# USB_GPIO_interface_V3.net
KiCad netlist of a schematic drawn in EAGLE
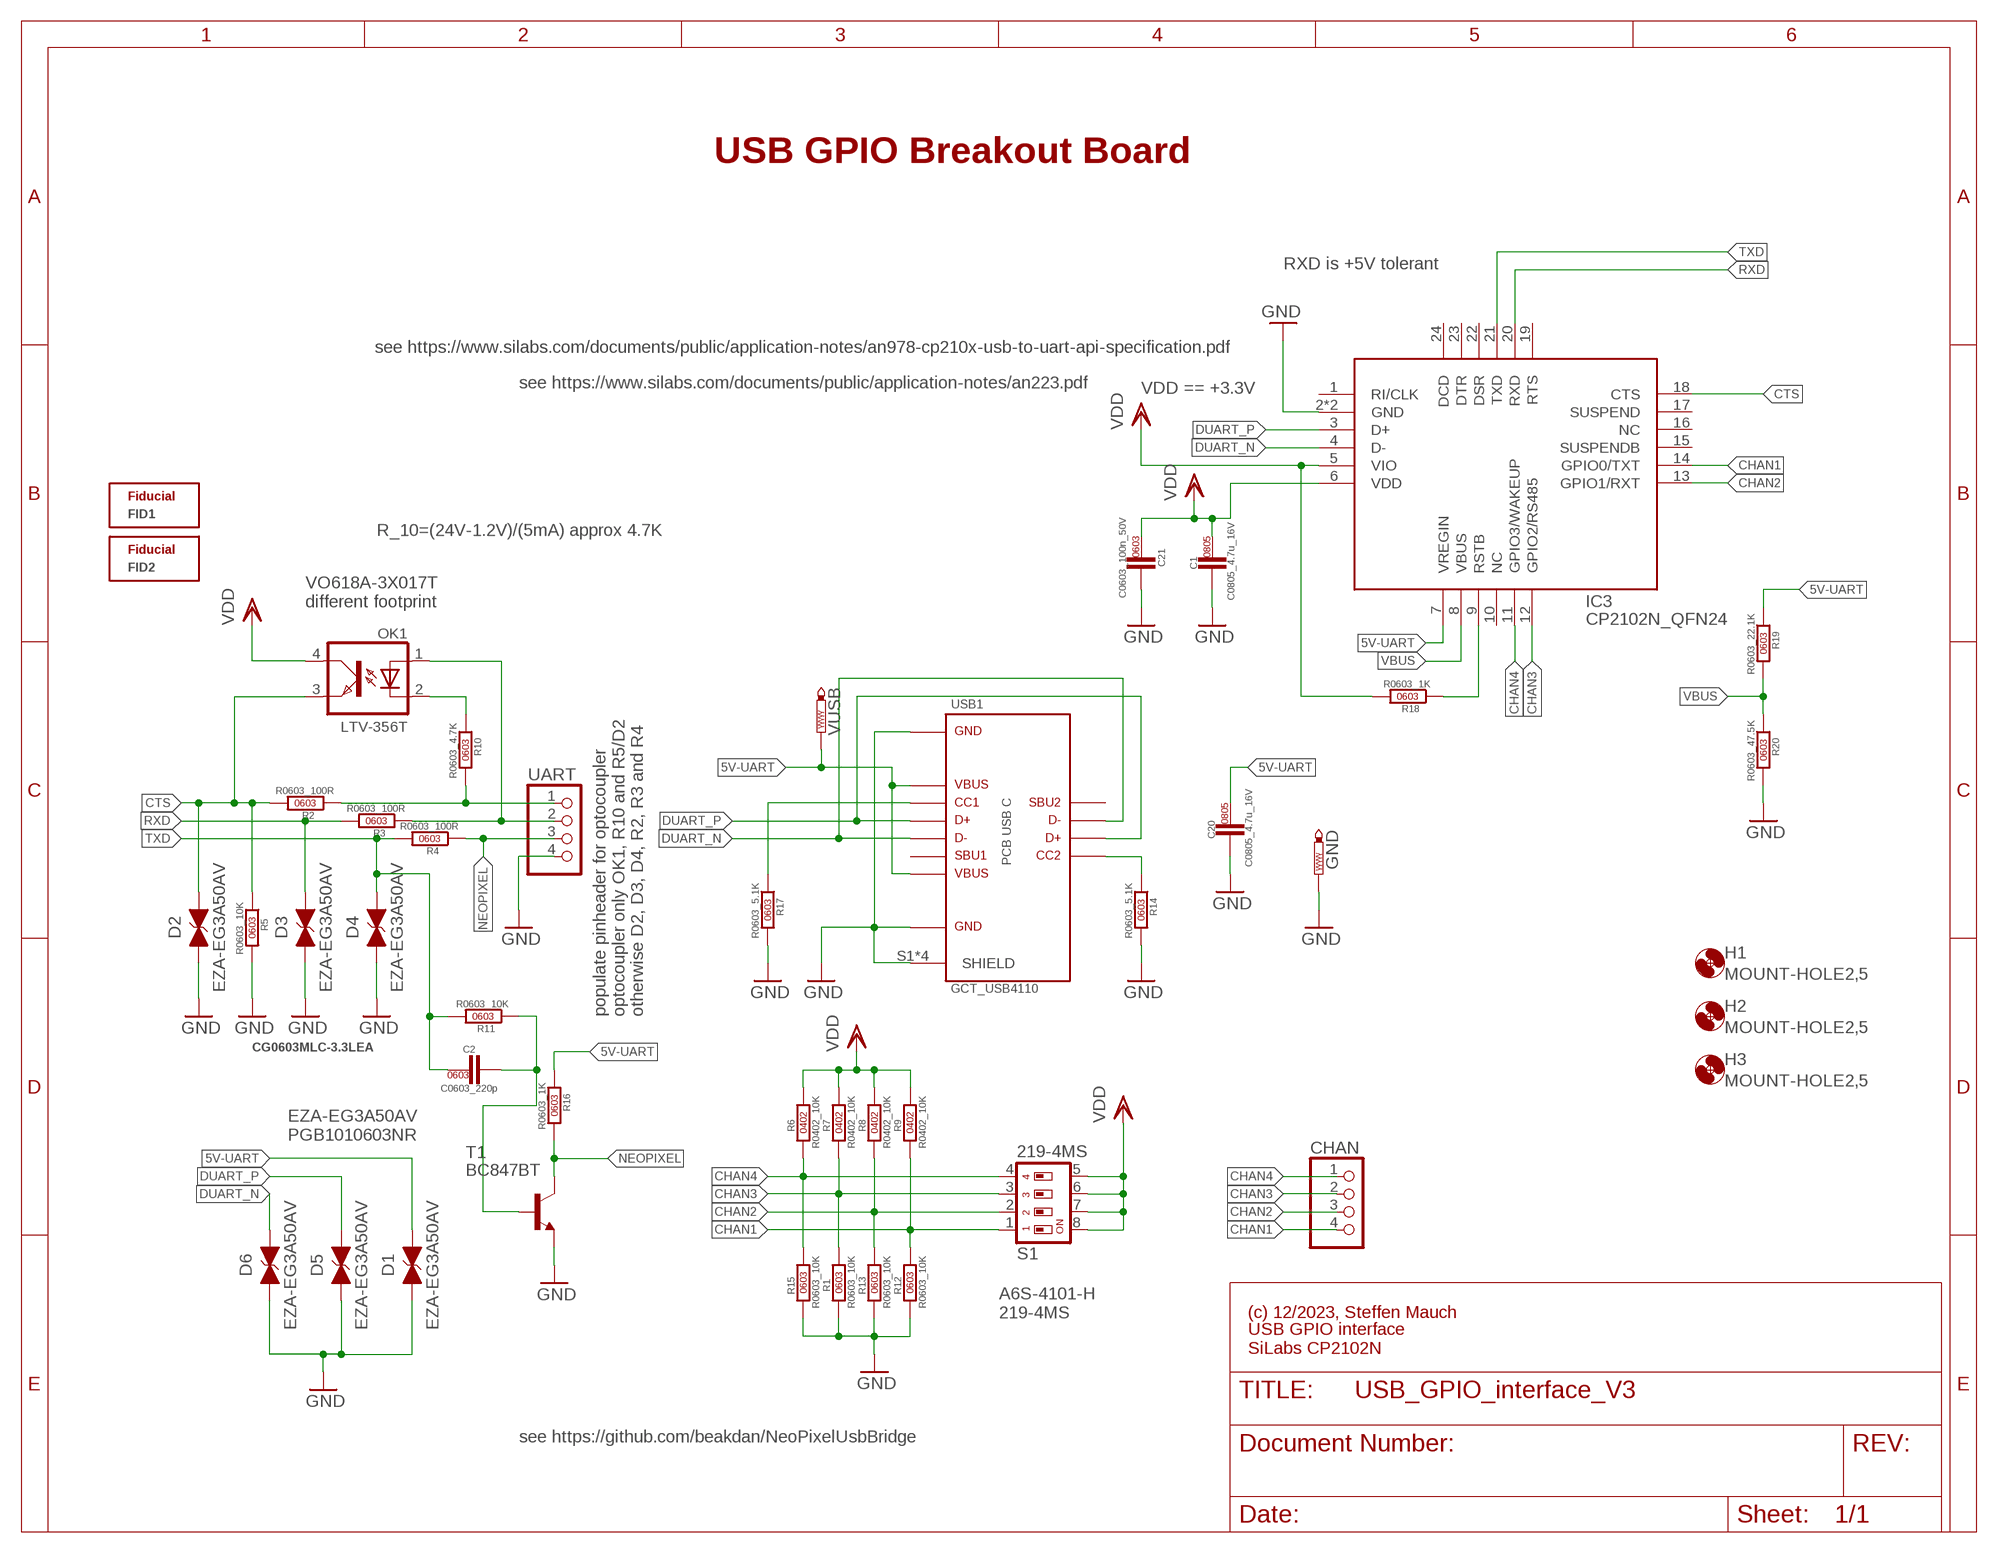
[diagram p0: schematic, sheet 1]

(export (version "E")
  (design (tool "Eeschema 10.0.6"))
  (components
    (comp (ref "C1")
      (value "C0805_4.7u_16V")
      (footprint "eagle-import:0805")
      (fields (field (name "MF") "generic"))
      (libsource (lib "eagle-import") (part "C_0805"))
    )
    (comp (ref "C2")
      (value "C0603_220p")
      (footprint "eagle-import:0603")
      (fields (field (name "MF") "generic"))
      (libsource (lib "eagle-import") (part "C_0603"))
    )
    (comp (ref "C20")
      (value "C0805_4.7u_16V")
      (footprint "eagle-import:0805")
      (fields (field (name "MF") "generic"))
      (libsource (lib "eagle-import") (part "C_0805"))
    )
    (comp (ref "C21")
      (value "C0603_100n_50V")
      (footprint "eagle-import:0603")
      (fields (field (name "MF") "generic"))
      (libsource (lib "eagle-import") (part "C_0603"))
    )
    (comp (ref "CHAN")
      (value "PINHD-1X4MOLEX")
      (footprint "eagle-import:1X04_MOLEX")
      (fields (field (name "MF") "JST") (field (name "MPN") "B4B-XH-A"))
      (libsource (lib "eagle-import") (part "PINHD-1X4MOLEX"))
    )
    (comp (ref "D1")
      (value "EZA-EG3A50AV")
      (footprint "eagle-import:TVS0603")
      (fields (field (name "MF") "Panasonic"))
      (libsource (lib "eagle-import") (part "EZA-EG3A50AV"))
    )
    (comp (ref "D2")
      (value "EZA-EG3A50AV")
      (footprint "eagle-import:TVS0603")
      (fields (field (name "MF") "Panasonic"))
      (libsource (lib "eagle-import") (part "EZA-EG3A50AV"))
    )
    (comp (ref "D3")
      (value "EZA-EG3A50AV")
      (footprint "eagle-import:TVS0603")
      (fields (field (name "MF") "Panasonic"))
      (libsource (lib "eagle-import") (part "EZA-EG3A50AV"))
    )
    (comp (ref "D4")
      (value "EZA-EG3A50AV")
      (footprint "eagle-import:TVS0603")
      (fields (field (name "MF") "Panasonic"))
      (libsource (lib "eagle-import") (part "EZA-EG3A50AV"))
    )
    (comp (ref "D5")
      (value "EZA-EG3A50AV")
      (footprint "eagle-import:TVS0603")
      (fields (field (name "MF") "Panasonic"))
      (libsource (lib "eagle-import") (part "EZA-EG3A50AV"))
    )
    (comp (ref "D6")
      (value "EZA-EG3A50AV")
      (footprint "eagle-import:TVS0603")
      (fields (field (name "MF") "Panasonic"))
      (libsource (lib "eagle-import") (part "EZA-EG3A50AV"))
    )
    (comp (ref "FID1")
      (value "FIDUCIAL-1MM")
      (footprint "eagle-import:FID-ROUND-1MM")
      (libsource (lib "eagle-import") (part "FIDUCIAL-1MM"))
    )
    (comp (ref "FID2")
      (value "FIDUCIAL-1MM")
      (footprint "eagle-import:FID-ROUND-1MM")
      (libsource (lib "eagle-import") (part "FIDUCIAL-1MM"))
    )
    (comp (ref "GND")
      (value "TESTPOINT0,8MM")
      (footprint "eagle-import:TESTPOINT-0.8MM")
      (libsource (lib "eagle-import") (part "TESTPOINT0,8MM"))
    )
    (comp (ref "H1")
      (value "MOUNT-HOLE2,5")
      (footprint "eagle-import:2,5")
      (libsource (lib "eagle-import") (part "MOUNT-HOLE2,5"))
    )
    (comp (ref "H2")
      (value "MOUNT-HOLE2,5")
      (footprint "eagle-import:2,5")
      (libsource (lib "eagle-import") (part "MOUNT-HOLE2,5"))
    )
    (comp (ref "H3")
      (value "MOUNT-HOLE2,5")
      (footprint "eagle-import:2,5")
      (libsource (lib "eagle-import") (part "MOUNT-HOLE2,5"))
    )
    (comp (ref "IC3")
      (value "CP2102N_QFN24")
      (footprint "eagle-import:QFN24-4X4")
      (fields (field (name "MF") "Silicon Labs") (field (name "MPN") "CP2102N-A02-GQFN24"))
      (libsource (lib "eagle-import") (part "CP2102N_QFN24"))
    )
    (comp (ref "OK1")
      (value "LTV-356T")
      (footprint "eagle-import:SMD4")
      (fields (field (name "MF") "LITEON"))
      (libsource (lib "eagle-import") (part "LTV-356T"))
    )
    (comp (ref "R1")
      (value "R0603_10K")
      (footprint "eagle-import:0603")
      (fields (field (name "MF") "generic"))
      (libsource (lib "eagle-import") (part "R0603_"))
    )
    (comp (ref "R2")
      (value "R0603_100R")
      (footprint "eagle-import:0603")
      (fields (field (name "MF") "generic"))
      (libsource (lib "eagle-import") (part "R0603_"))
    )
    (comp (ref "R3")
      (value "R0603_100R")
      (footprint "eagle-import:0603")
      (fields (field (name "MF") "generic"))
      (libsource (lib "eagle-import") (part "R0603_"))
    )
    (comp (ref "R4")
      (value "R0603_100R")
      (footprint "eagle-import:0603")
      (fields (field (name "MF") "generic"))
      (libsource (lib "eagle-import") (part "R0603_"))
    )
    (comp (ref "R5")
      (value "R0603_10K")
      (footprint "eagle-import:0603")
      (fields (field (name "MF") "generic"))
      (libsource (lib "eagle-import") (part "R0603_"))
    )
    (comp (ref "R6")
      (value "R0402_10K")
      (footprint "eagle-import:0402")
      (fields (field (name "MF") "generic"))
      (libsource (lib "eagle-import") (part "R0402_"))
    )
    (comp (ref "R7")
      (value "R0402_10K")
      (footprint "eagle-import:0402")
      (fields (field (name "MF") "generic"))
      (libsource (lib "eagle-import") (part "R0402_"))
    )
    (comp (ref "R8")
      (value "R0402_10K")
      (footprint "eagle-import:0402")
      (fields (field (name "MF") "generic"))
      (libsource (lib "eagle-import") (part "R0402_"))
    )
    (comp (ref "R9")
      (value "R0402_10K")
      (footprint "eagle-import:0402")
      (fields (field (name "MF") "generic"))
      (libsource (lib "eagle-import") (part "R0402_"))
    )
    (comp (ref "R10")
      (value "R0603_4.7K")
      (footprint "eagle-import:0603")
      (fields (field (name "MF") "generic"))
      (libsource (lib "eagle-import") (part "R0603_"))
    )
    (comp (ref "R11")
      (value "R0603_10K")
      (footprint "eagle-import:0603")
      (fields (field (name "MF") "generic"))
      (libsource (lib "eagle-import") (part "R0603_"))
    )
    (comp (ref "R12")
      (value "R0603_10K")
      (footprint "eagle-import:0603")
      (fields (field (name "MF") "generic"))
      (libsource (lib "eagle-import") (part "R0603_"))
    )
    (comp (ref "R13")
      (value "R0603_10K")
      (footprint "eagle-import:0603")
      (fields (field (name "MF") "generic"))
      (libsource (lib "eagle-import") (part "R0603_"))
    )
    (comp (ref "R14")
      (value "R0603_5.1K")
      (footprint "eagle-import:0603")
      (fields (field (name "MF") "generic"))
      (libsource (lib "eagle-import") (part "R0603_"))
    )
    (comp (ref "R15")
      (value "R0603_10K")
      (footprint "eagle-import:0603")
      (fields (field (name "MF") "generic"))
      (libsource (lib "eagle-import") (part "R0603_"))
    )
    (comp (ref "R16")
      (value "R0603_1K")
      (footprint "eagle-import:0603")
      (fields (field (name "MF") "generic"))
      (libsource (lib "eagle-import") (part "R0603_"))
    )
    (comp (ref "R17")
      (value "R0603_5.1K")
      (footprint "eagle-import:0603")
      (fields (field (name "MF") "generic"))
      (libsource (lib "eagle-import") (part "R0603_"))
    )
    (comp (ref "R18")
      (value "R0603_1K")
      (footprint "eagle-import:0603")
      (fields (field (name "MF") "generic"))
      (libsource (lib "eagle-import") (part "R0603_"))
    )
    (comp (ref "R19")
      (value "R0603_22.1K")
      (footprint "eagle-import:0603")
      (fields (field (name "MF") "generic"))
      (libsource (lib "eagle-import") (part "R0603_"))
    )
    (comp (ref "R20")
      (value "R0603_47.5K")
      (footprint "eagle-import:0603")
      (fields (field (name "MF") "generic"))
      (libsource (lib "eagle-import") (part "R0603_"))
    )
    (comp (ref "S1")
      (value "219-4MS")
      (footprint "eagle-import:SMS-004")
      (fields (field (name "MF") "CTS Components"))
      (libsource (lib "eagle-import") (part "219-4MS"))
    )
    (comp (ref "T1")
      (value "BC847BT")
      (footprint "eagle-import:SOT-523-3")
      (libsource (lib "eagle-import") (part "BC847BT"))
    )
    (comp (ref "UART")
      (value "PINHD-1X4MOLEX")
      (footprint "eagle-import:1X04_MOLEX")
      (fields (field (name "MF") "JST") (field (name "MPN") "B4B-XH-A"))
      (libsource (lib "eagle-import") (part "PINHD-1X4MOLEX"))
    )
    (comp (ref "USB1")
      (value "GCT_USB4110")
      (footprint "eagle-import:GCT_USB4110")
      (libsource (lib "eagle-import") (part "GCT_USB4110"))
    )
    (comp (ref "VUSB")
      (value "TESTPOINT0,8MM")
      (footprint "eagle-import:TESTPOINT-0.8MM")
      (libsource (lib "eagle-import") (part "TESTPOINT0,8MM"))
    )
  )
  (nets
    (net (code "1") (name "5V-UART") (class "Default")
      (node (ref "C20") (pin "1") (pinfunction "1_1") (pintype "passive"))
      (node (ref "D1") (pin "2") (pinfunction "P$2_2") (pintype "bidirectional"))
      (node (ref "IC3") (pin "7") (pinfunction "VREGIN_7") (pintype "bidirectional"))
      (node (ref "R16") (pin "1") (pinfunction "1_1") (pintype "passive"))
      (node (ref "R19") (pin "1") (pinfunction "1_1") (pintype "passive"))
      (node (ref "USB1") (pin "A4/B9") (pinfunction "A4_A4/B9") (pintype "bidirectional"))
      (node (ref "USB1") (pin "B4/A9") (pinfunction "A9_B4/A9") (pintype "bidirectional"))
      (node (ref "VUSB") (pin "P$1") (pinfunction "TP_P$1") (pintype "input"))
    )
    (net (code "2") (name "CHAN1") (class "Default")
      (node (ref "CHAN") (pin "4") (pinfunction "4_4") (pintype "passive"))
      (node (ref "IC3") (pin "14") (pinfunction "GPIO0/TXT_14") (pintype "bidirectional"))
      (node (ref "R12") (pin "2") (pinfunction "2_2") (pintype "passive"))
      (node (ref "R9") (pin "1") (pinfunction "1_1") (pintype "passive"))
      (node (ref "S1") (pin "1") (pinfunction "1_1") (pintype "passive"))
    )
    (net (code "3") (name "CHAN2") (class "Default")
      (node (ref "CHAN") (pin "3") (pinfunction "3_3") (pintype "passive"))
      (node (ref "IC3") (pin "13") (pinfunction "GPIO1/RXT_13") (pintype "bidirectional"))
      (node (ref "R13") (pin "2") (pinfunction "2_2") (pintype "passive"))
      (node (ref "R8") (pin "1") (pinfunction "1_1") (pintype "passive"))
      (node (ref "S1") (pin "2") (pinfunction "2_2") (pintype "passive"))
    )
    (net (code "4") (name "CHAN3") (class "Default")
      (node (ref "CHAN") (pin "2") (pinfunction "2_2") (pintype "passive"))
      (node (ref "IC3") (pin "12") (pinfunction "GPIO2/RS485_12") (pintype "bidirectional"))
      (node (ref "R1") (pin "2") (pinfunction "2_2") (pintype "passive"))
      (node (ref "R7") (pin "1") (pinfunction "1_1") (pintype "passive"))
      (node (ref "S1") (pin "3") (pinfunction "3_3") (pintype "passive"))
    )
    (net (code "5") (name "CHAN4") (class "Default")
      (node (ref "CHAN") (pin "1") (pinfunction "1_1") (pintype "passive"))
      (node (ref "IC3") (pin "11") (pinfunction "GPIO3/WAKEUP_11") (pintype "bidirectional"))
      (node (ref "R15") (pin "2") (pinfunction "2_2") (pintype "passive"))
      (node (ref "R6") (pin "1") (pinfunction "1_1") (pintype "passive"))
      (node (ref "S1") (pin "4") (pinfunction "4_4") (pintype "passive"))
    )
    (net (code "6") (name "CTS") (class "Default")
      (node (ref "D2") (pin "2") (pinfunction "P$2_2") (pintype "bidirectional"))
      (node (ref "IC3") (pin "18") (pinfunction "CTS_18") (pintype "bidirectional"))
      (node (ref "OK1") (pin "3") (pinfunction "E_3") (pintype "passive"))
      (node (ref "R2") (pin "2") (pinfunction "2_2") (pintype "passive"))
      (node (ref "R5") (pin "1") (pinfunction "1_1") (pintype "passive"))
    )
    (net (code "7") (name "DUART_N") (class "Default")
      (node (ref "D6") (pin "2") (pinfunction "P$2_2") (pintype "bidirectional"))
      (node (ref "IC3") (pin "4") (pinfunction "D-_4") (pintype "bidirectional"))
      (node (ref "USB1") (pin "A7") (pinfunction "A7_A7") (pintype "bidirectional"))
      (node (ref "USB1") (pin "B7") (pinfunction "B7_B7") (pintype "bidirectional"))
    )
    (net (code "8") (name "DUART_P") (class "Default")
      (node (ref "D5") (pin "2") (pinfunction "P$2_2") (pintype "bidirectional"))
      (node (ref "IC3") (pin "3") (pinfunction "D+_3") (pintype "bidirectional"))
      (node (ref "USB1") (pin "A6") (pinfunction "A6_A6") (pintype "bidirectional"))
      (node (ref "USB1") (pin "B6") (pinfunction "B6_B6") (pintype "bidirectional"))
    )
    (net (code "9") (name "GND") (class "Default")
      (node (ref "C1") (pin "2") (pinfunction "2_2") (pintype "passive"))
      (node (ref "C20") (pin "2") (pinfunction "2_2") (pintype "passive"))
      (node (ref "C21") (pin "2") (pinfunction "2_2") (pintype "passive"))
      (node (ref "D1") (pin "1") (pinfunction "P$1_1") (pintype "bidirectional"))
      (node (ref "D2") (pin "1") (pinfunction "P$1_1") (pintype "bidirectional"))
      (node (ref "D3") (pin "1") (pinfunction "P$1_1") (pintype "bidirectional"))
      (node (ref "D4") (pin "1") (pinfunction "P$1_1") (pintype "bidirectional"))
      (node (ref "D5") (pin "1") (pinfunction "P$1_1") (pintype "bidirectional"))
      (node (ref "D6") (pin "1") (pinfunction "P$1_1") (pintype "bidirectional"))
      (node (ref "GND") (pin "P$1") (pinfunction "TP_P$1") (pintype "input"))
      (node (ref "IC3") (pin "2") (pinfunction "GND_2") (pintype "bidirectional"))
      (node (ref "IC3") (pin "EXP") (pinfunction "GND_EXP") (pintype "bidirectional"))
      (node (ref "R1") (pin "1") (pinfunction "1_1") (pintype "passive"))
      (node (ref "R12") (pin "1") (pinfunction "1_1") (pintype "passive"))
      (node (ref "R13") (pin "1") (pinfunction "1_1") (pintype "passive"))
      (node (ref "R14") (pin "2") (pinfunction "2_2") (pintype "passive"))
      (node (ref "R15") (pin "1") (pinfunction "1_1") (pintype "passive"))
      (node (ref "R17") (pin "2") (pinfunction "2_2") (pintype "passive"))
      (node (ref "R20") (pin "2") (pinfunction "2_2") (pintype "passive"))
      (node (ref "R5") (pin "2") (pinfunction "2_2") (pintype "passive"))
      (node (ref "T1") (pin "2") (pinfunction "E_2") (pintype "passive"))
      (node (ref "UART") (pin "4") (pinfunction "4_4") (pintype "passive"))
      (node (ref "USB1") (pin "A1/B12") (pinfunction "A1_A1/B12") (pintype "bidirectional"))
      (node (ref "USB1") (pin "B!/A12") (pinfunction "A12_B!/A12") (pintype "bidirectional"))
      (node (ref "USB1") (pin "S1") (pinfunction "SHIELD_S1") (pintype "bidirectional"))
      (node (ref "USB1") (pin "S2") (pinfunction "SHIELD_S2") (pintype "bidirectional"))
      (node (ref "USB1") (pin "S3") (pinfunction "SHIELD_S3") (pintype "bidirectional"))
      (node (ref "USB1") (pin "S4") (pinfunction "SHIELD_S4") (pintype "bidirectional"))
    )
    (net (code "10") (name "NEOPIXEL") (class "Default")
      (node (ref "R16") (pin "2") (pinfunction "2_2") (pintype "passive"))
      (node (ref "R4") (pin "1") (pinfunction "1_1") (pintype "passive"))
      (node (ref "T1") (pin "3") (pinfunction "C_3") (pintype "passive"))
      (node (ref "UART") (pin "3") (pinfunction "3_3") (pintype "passive"))
    )
    (net (code "11") (name "Net-(IC3-RSTB)") (class "Default")
      (node (ref "IC3") (pin "9") (pinfunction "RSTB_9") (pintype "bidirectional"))
      (node (ref "R18") (pin "1") (pinfunction "1_1") (pintype "passive"))
    )
    (net (code "12") (name "Net-(OK1-A)") (class "Default")
      (node (ref "OK1") (pin "1") (pinfunction "A_1") (pintype "passive"))
      (node (ref "R3") (pin "1") (pinfunction "1_1") (pintype "passive"))
      (node (ref "UART") (pin "2") (pinfunction "2_2") (pintype "passive"))
    )
    (net (code "13") (name "Net-(OK1-K)") (class "Default")
      (node (ref "OK1") (pin "2") (pinfunction "K_2") (pintype "passive"))
      (node (ref "R10") (pin "1") (pinfunction "1_1") (pintype "passive"))
    )
    (net (code "14") (name "Net-(R10-Pad2)") (class "Default")
      (node (ref "R10") (pin "2") (pinfunction "2_2") (pintype "passive"))
      (node (ref "R2") (pin "1") (pinfunction "1_1") (pintype "passive"))
      (node (ref "UART") (pin "1") (pinfunction "1_1") (pintype "passive"))
    )
    (net (code "15") (name "Net-(R14-Pad1)") (class "Default")
      (node (ref "R14") (pin "1") (pinfunction "1_1") (pintype "passive"))
      (node (ref "USB1") (pin "B5") (pinfunction "B5_B5") (pintype "bidirectional"))
    )
    (net (code "16") (name "Net-(R17-Pad1)") (class "Default")
      (node (ref "R17") (pin "1") (pinfunction "1_1") (pintype "passive"))
      (node (ref "USB1") (pin "A5") (pinfunction "A5_A5") (pintype "bidirectional"))
    )
    (net (code "17") (name "Net-(T1-B)") (class "Default")
      (node (ref "C2") (pin "2") (pinfunction "2_2") (pintype "passive"))
      (node (ref "R11") (pin "1") (pinfunction "1_1") (pintype "passive"))
      (node (ref "T1") (pin "1") (pinfunction "B_1") (pintype "passive"))
    )
    (net (code "18") (name "RXD") (class "Default")
      (node (ref "D3") (pin "2") (pinfunction "P$2_2") (pintype "bidirectional"))
      (node (ref "IC3") (pin "20") (pinfunction "RXD_20") (pintype "bidirectional"))
      (node (ref "R3") (pin "2") (pinfunction "2_2") (pintype "passive"))
    )
    (net (code "19") (name "TXD") (class "Default")
      (node (ref "C2") (pin "1") (pinfunction "1_1") (pintype "passive"))
      (node (ref "D4") (pin "2") (pinfunction "P$2_2") (pintype "bidirectional"))
      (node (ref "IC3") (pin "21") (pinfunction "TXD_21") (pintype "bidirectional"))
      (node (ref "R11") (pin "2") (pinfunction "2_2") (pintype "passive"))
      (node (ref "R4") (pin "2") (pinfunction "2_2") (pintype "passive"))
    )
    (net (code "20") (name "VBUS") (class "Default")
      (node (ref "IC3") (pin "8") (pinfunction "VBUS_8") (pintype "bidirectional"))
      (node (ref "R19") (pin "2") (pinfunction "2_2") (pintype "passive"))
      (node (ref "R20") (pin "1") (pinfunction "1_1") (pintype "passive"))
    )
    (net (code "21") (name "VDD") (class "Default")
      (node (ref "C1") (pin "1") (pinfunction "1_1") (pintype "passive"))
      (node (ref "C21") (pin "1") (pinfunction "1_1") (pintype "passive"))
      (node (ref "IC3") (pin "5") (pinfunction "VIO_5") (pintype "bidirectional"))
      (node (ref "IC3") (pin "6") (pinfunction "VDD_6") (pintype "bidirectional"))
      (node (ref "OK1") (pin "4") (pinfunction "C_4") (pintype "passive"))
      (node (ref "R18") (pin "2") (pinfunction "2_2") (pintype "passive"))
      (node (ref "R6") (pin "2") (pinfunction "2_2") (pintype "passive"))
      (node (ref "R7") (pin "2") (pinfunction "2_2") (pintype "passive"))
      (node (ref "R8") (pin "2") (pinfunction "2_2") (pintype "passive"))
      (node (ref "R9") (pin "2") (pinfunction "2_2") (pintype "passive"))
      (node (ref "S1") (pin "5") (pinfunction "5_5") (pintype "passive"))
      (node (ref "S1") (pin "6") (pinfunction "6_6") (pintype "passive"))
      (node (ref "S1") (pin "7") (pinfunction "7_7") (pintype "passive"))
      (node (ref "S1") (pin "8") (pinfunction "8_8") (pintype "passive"))
    )
    (net (code "22") (name "unconnected-(IC3-DCD-Pad24)") (class "Default")
      (node (ref "IC3") (pin "24") (pinfunction "DCD_24") (pintype "bidirectional"))
    )
    (net (code "23") (name "unconnected-(IC3-DSR-Pad22)") (class "Default")
      (node (ref "IC3") (pin "22") (pinfunction "DSR_22") (pintype "bidirectional"))
    )
    (net (code "24") (name "unconnected-(IC3-DTR-Pad23)") (class "Default")
      (node (ref "IC3") (pin "23") (pinfunction "DTR_23") (pintype "bidirectional"))
    )
    (net (code "25") (name "unconnected-(IC3-NC-Pad10)") (class "Default")
      (node (ref "IC3") (pin "10") (pinfunction "NC_10") (pintype "bidirectional"))
    )
    (net (code "26") (name "unconnected-(IC3-NC-Pad16)") (class "Default")
      (node (ref "IC3") (pin "16") (pinfunction "NC_16") (pintype "bidirectional"))
    )
    (net (code "27") (name "unconnected-(IC3-RI{slash}CLK-Pad1)") (class "Default")
      (node (ref "IC3") (pin "1") (pinfunction "RI/CLK_1") (pintype "bidirectional"))
    )
    (net (code "28") (name "unconnected-(IC3-RTS-Pad19)") (class "Default")
      (node (ref "IC3") (pin "19") (pinfunction "RTS_19") (pintype "bidirectional"))
    )
    (net (code "29") (name "unconnected-(IC3-SUSPEND-Pad17)") (class "Default")
      (node (ref "IC3") (pin "17") (pinfunction "SUSPEND_17") (pintype "bidirectional"))
    )
    (net (code "30") (name "unconnected-(IC3-SUSPENDB-Pad15)") (class "Default")
      (node (ref "IC3") (pin "15") (pinfunction "SUSPENDB_15") (pintype "bidirectional"))
    )
    (net (code "31") (name "unconnected-(USB1-PadA8)") (class "Default")
      (node (ref "USB1") (pin "A8") (pinfunction "A8_A8") (pintype "bidirectional"))
    )
    (net (code "32") (name "unconnected-(USB1-PadB8)") (class "Default")
      (node (ref "USB1") (pin "B8") (pinfunction "B8_B8") (pintype "bidirectional"))
    )
  )
)
